# Sheet1.net
KiCad netlist of a schematic drawn in Altium Designer
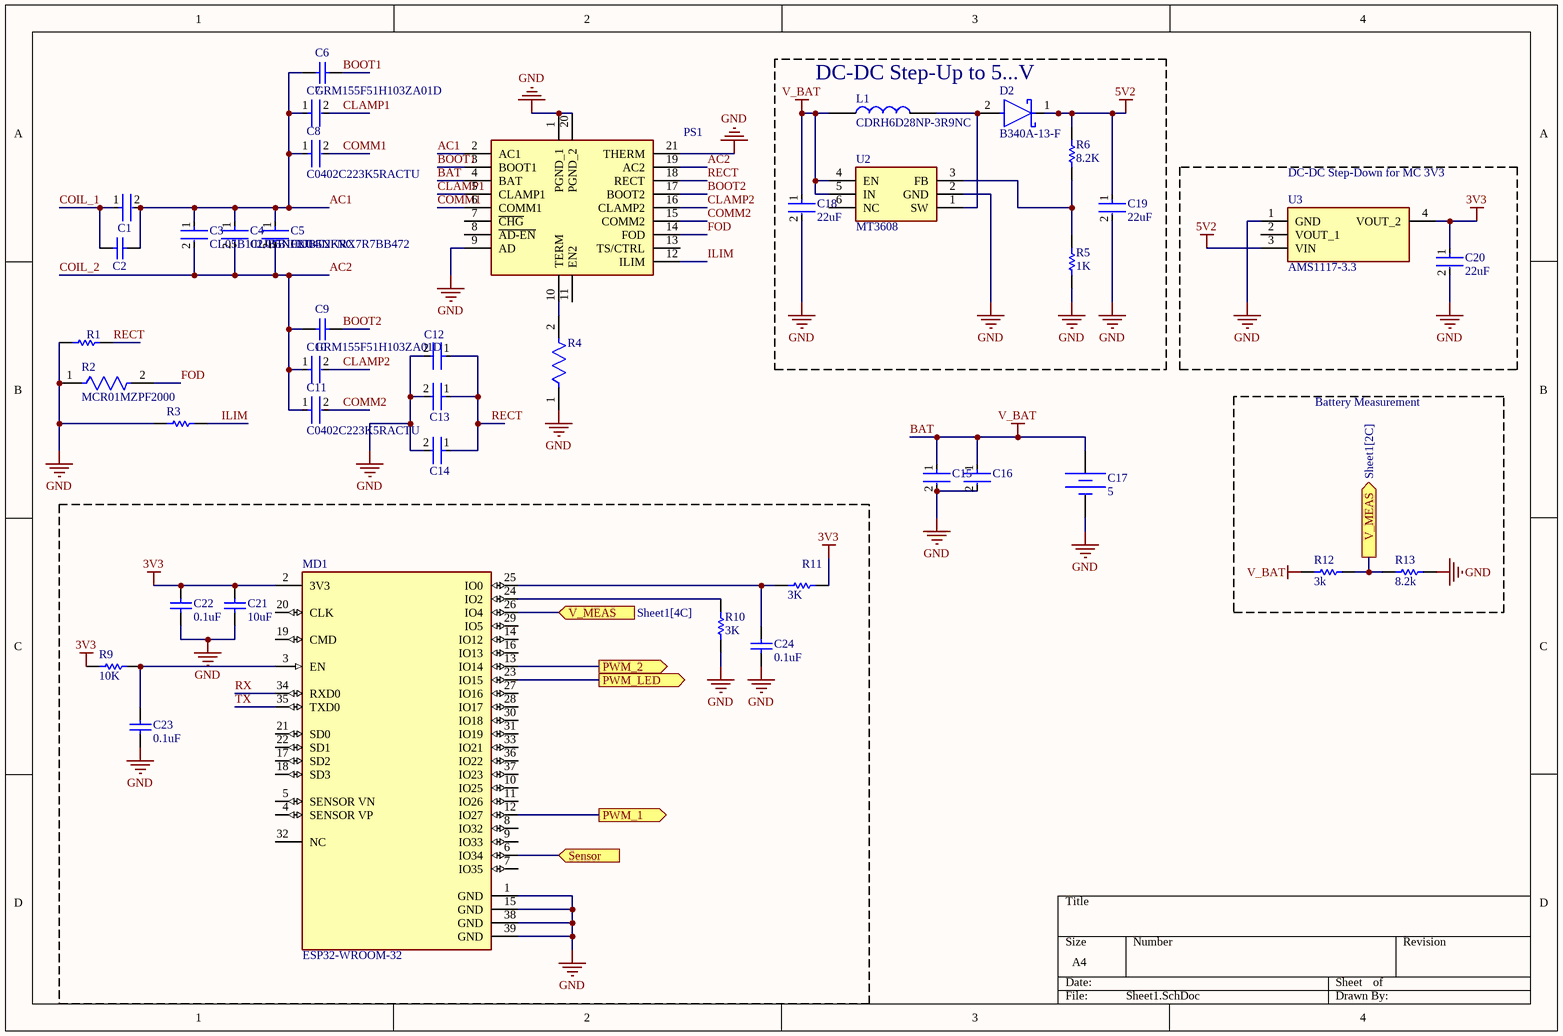
[diagram p0: Sheet1.SchDoc]

(export (version "E")
  (design (tool "Eeschema 10.0.6"))
  (components
    (comp (ref "C1")
      (value "CL05A474KA5NNNC")
      (footprint "FP-CL545-IPC_C")
      (description "Cap Ceramic 470nF 25V X5R ±10% SMD 0402 +85°C Paper T/R")
      (fields (field (name "TOLERANCE") "10%"))
      (libsource (lib "Altium Content Vault") (part "b4654b650e69147ec39a6b967a45e02"))
    )
    (comp (ref "C2")
      (value "04023D104KAT2A")
      (footprint "CAPC1005X56X25NL10T15")
      (fields (field (name "MANUFACTURER") "AVX Interconnect / Elco"))
      (libsource (lib "Altium Content Vault") (part "CAP"))
    )
    (comp (ref "C3")
      (value "CL05B102JB5NFNC")
      (footprint "FP-CL956-IPC_C")
      (description "Cap Ceramic 1nF 50V X7R ±5% SMD 0402 +125°C Paper T/R")
      (fields (field (name "TOLERANCE") "5%"))
      (libsource (lib "Altium Content Vault") (part "b4654b650e69147ec39a6b967a45e02"))
    )
    (comp (ref "C4")
      (value "CL05B102JB5NFNC")
      (footprint "FP-CL956-IPC_C")
      (description "Cap Ceramic 1nF 50V X7R ±5% SMD 0402 +125°C Paper T/R")
      (fields (field (name "TOLERANCE") "5%"))
      (libsource (lib "Altium Content Vault") (part "b4654b650e69147ec39a6b967a45e02"))
    )
    (comp (ref "C5")
      (value "CC0402KRX7R7BB472")
      (footprint "FP-CC0402-MFG")
      (description "CAP CER 4700PF 16V X7R 0402")
      (fields
        (field (name "OCTOPART") "https://octopart.com/cc0402krx7r7bb472-yageo-44648962")
        (field (name "MANUFACTURER") "YAGEO")
      )
      (libsource (lib "Altium Content Vault") (part "11868f565c42a9108669ba33697ecf6"))
    )
    (comp (ref "C6")
      (value "GRM155F51H103ZA01D")
      (footprint "CAPC1005X55X25ML05T10")
      (fields (field (name "MANUFACTURER") "Murata"))
      (libsource (lib "Altium Content Vault") (part "CAP"))
    )
    (comp (ref "C7")
      (value "C1005X5R1E474K050BB")
      (footprint "FP-C1005-050-0_05-IPC_B")
      (description "Multilayer Ceramic Capacitors 470nF ±10% 25V X5R SMD 0402")
      (fields (field (name "VOLTAGE") "25V") (field (name "TOLERANCE") "10%"))
      (libsource (lib "Altium Content Vault") (part "b4654b650e69147ec39a6b967a45e02"))
    )
    (comp (ref "C8")
      (value "C0402C223K5RACTU")
      (footprint "FP-C0402-BB-MFG")
      (description "CAP CER 0.022UF 50V 10% X7R 0402")
      (fields (field (name "TOLERANCE") "0.1") (field (name "MANUFACTURER") "Kemet"))
      (libsource (lib "Altium Content Vault") (part "b4654b650e69147ec39a6b967a45e02"))
    )
    (comp (ref "C9")
      (value "GRM155F51H103ZA01D")
      (footprint "CAPC1005X55X25ML05T10")
      (fields (field (name "MANUFACTURER") "Murata"))
      (libsource (lib "Altium Content Vault") (part "CAP"))
    )
    (comp (ref "C10")
      (value "C1005X5R1E474K050BB")
      (footprint "FP-C1005-050-0_05-IPC_B")
      (description "Multilayer Ceramic Capacitors 470nF ±10% 25V X5R SMD 0402")
      (fields (field (name "VOLTAGE") "25V") (field (name "TOLERANCE") "10%"))
      (libsource (lib "Altium Content Vault") (part "b4654b650e69147ec39a6b967a45e02"))
    )
    (comp (ref "C11")
      (value "C0402C223K5RACTU")
      (footprint "FP-C0402-BB-MFG")
      (description "CAP CER 0.022UF 50V 10% X7R 0402")
      (fields (field (name "TOLERANCE") "0.1") (field (name "MANUFACTURER") "Kemet"))
      (libsource (lib "Altium Content Vault") (part "b4654b650e69147ec39a6b967a45e02"))
    )
    (comp (ref "C12")
      (value "CL10A106MA8NRNC")
      (footprint "FP-CL10-IPC_C")
      (description "Cap Ceramic 10uF 25V X5R ±20% Pad SMD 0603 +85°C T/R")
      (fields (field (name "TOLERANCE") "20%"))
      (libsource (lib "Altium Content Vault") (part "b4654b650e69147ec39a6b967a45e02"))
    )
    (comp (ref "C13")
      (value "CL10A106MA8NRNC")
      (footprint "FP-CL10-IPC_C")
      (description "Cap Ceramic 10uF 25V X5R ±20% Pad SMD 0603 +85°C T/R")
      (fields (field (name "TOLERANCE") "20%"))
      (libsource (lib "Altium Content Vault") (part "b4654b650e69147ec39a6b967a45e02"))
    )
    (comp (ref "C14")
      (value "C0603X5R1E104K030BB")
      (footprint "FP-C0603-030-0_03-IPC_C")
      (description "Multilayer Ceramic Capacitors 100nF ±10% 25V X5R SMD 0201")
      (fields (field (name "TOLERANCE") "10%"))
      (libsource (lib "Altium Content Vault") (part "02cd4be3c70576c341d710602a673aa"))
    )
    (comp (ref "C15")
      (value "EMK105BJ105KV-F")
      (footprint "FP-0402-L_1_0_0_05-W_0_5-IPC_A")
      (description "None")
      (fields (field (name "TOLERANCE") "10%"))
      (libsource (lib "Altium Content Vault") (part "b4654b650e69147ec39a6b967a45e02"))
    )
    (comp (ref "C16")
      (value "GRM033R60J104KE19J")
      (footprint "FP-GRM033-0_03-MFG")
      (description "Chip Multilayer Ceramic Capacitors for General Purpose, 0201, 0.10uF, X5R, 15%, 10%, 6.3V")
      (fields (field (name "TOLERANCE") "10%"))
      (libsource (lib "Altium Content Vault") (part "b4654b650e69147ec39a6b967a45e02"))
    )
    (comp (ref "C17")
      (value "Constant Voltage Source")
      (fields (field (name "DC MAGNITUDE") "5"))
      (libsource (lib "Simulation Generic Components") (part "Battery"))
    )
    (comp (ref "C18")
      (value "22uF")
      (footprint "FP-GRM31C-0_2-e0_3_0_8-IPC_C")
      (description "Chip Multilayer Ceramic Capacitors for General Purpose, 1206, 22uF, X7R, 15%, 10%, 10V")
      (fields (field (name "TOLERANCE") "10%"))
      (libsource (lib "Altium Content Vault") (part "02cd4be3c70576c341d710602a673aa"))
    )
    (comp (ref "C19")
      (value "22uF")
      (footprint "FP-GRM31C-0_2-e0_3_0_8-IPC_C")
      (description "Chip Multilayer Ceramic Capacitors for General Purpose, 1206, 22uF, X7R, 15%, 10%, 10V")
      (fields (field (name "TOLERANCE") "10%"))
      (libsource (lib "Altium Content Vault") (part "02cd4be3c70576c341d710602a673aa"))
    )
    (comp (ref "C20")
      (value "22uF")
      (footprint "FP-GRM31C-0_2-e0_3_0_8-IPC_C")
      (description "Chip Multilayer Ceramic Capacitors for General Purpose, 1206, 22uF, X7R, 15%, 10%, 10V")
      (fields (field (name "TOLERANCE") "10%"))
      (libsource (lib "Altium Content Vault") (part "02cd4be3c70576c341d710602a673aa"))
    )
    (comp (ref "C21")
      (value "10uF")
      (footprint "CAPC1005X55X30LL05T10")
      (fields (field (name "MANUFACTURER") "Kemet") (field (name "PART NUMBER") "C0402C104K4RACTU"))
      (libsource (lib "Altium Content Vault") (part "CAP"))
    )
    (comp (ref "C22")
      (value "0.1uF")
      (footprint "CAPC1005X55X30LL05T10")
      (fields (field (name "MANUFACTURER") "Kemet") (field (name "PART NUMBER") "C0402C104K4RACTU"))
      (libsource (lib "Altium Content Vault") (part "CAP"))
    )
    (comp (ref "C23")
      (value "0.1uF")
      (footprint "CAPC1005X55X30LL05T10")
      (fields (field (name "MANUFACTURER") "Kemet") (field (name "PART NUMBER") "C0402C104K4RACTU"))
      (libsource (lib "Altium Content Vault") (part "CAP"))
    )
    (comp (ref "C24")
      (value "0.1uF")
      (footprint "CAPC1005X55X30LL05T10")
      (fields (field (name "MANUFACTURER") "Kemet") (field (name "PART NUMBER") "C0402C104K4RACTU"))
      (libsource (lib "Altium Content Vault") (part "CAP"))
    )
    (comp (ref "D2")
      (value "B340A-13-F")
      (footprint "FP-SMA-MFG")
      (description "DIODE SCHOTTKY 40V 3A SMA")
      (fields (field (name "VOLTAGE") "40V"))
      (libsource (lib "Altium Content Vault") (part "1d6ec82d83fb6aee721767c19dac4b9"))
    )
    (comp (ref "L1")
      (value "CDRH6D28NP-3R9NC")
      (footprint "INDPM6767X300N")
      (description "Inductor Power Shielded Drum Core 3.9uH 30% 100KHz Ferrite 2.6A 27mOhm DCR T/R")
      (fields (field (name "MOUSER PART NUMBER") "851-CDRH6D28NP-3R9NC"))
      (libsource (lib "CDRH6D28NP-3R9NC") (part "CDRH6D28NP-3R9NC"))
    )
    (comp (ref "MD1")
      (value "ESP32-WROOM-32")
      (footprint "FP-ESP32-WROOM-32-MFG")
      (description "RX TXRX MOD WIFI SURFACE MOUNT")
      (libsource (lib "Altium Content Vault") (part "ee866abf0b6c51247b7f5cdebf2f250"))
    )
    (comp (ref "PS1")
      (value "BQ51050BRHLT")
      (footprint "SamacSys:RHL(R-PVQFN-N20)_1")
      (description "Power Supply")
      (fields (field (name "MOUSER PART NUMBER") "595-BQ51050BRHLT"))
      (libsource (lib "*") (part "BQ51050BRHLT"))
    )
    (comp (ref "R1")
      (value "ERJ-1GNF4122C")
      (footprint "RESC0603X26X15ML03T05")
      (fields (field (name "MANUFACTURER") "Panasonic"))
      (libsource (lib "Altium Content Vault") (part "RES"))
    )
    (comp (ref "R2")
      (value "MCR01MZPF2000")
      (footprint "FP-MCR01-IPC_B")
      (description "Thick Film Chip Resistor, 0402, 200Ω, 1%, 100ppm/°C, 0.063W, 50V")
      (fields (field (name "TOLERANCE") "1%"))
      (libsource (lib "Altium Content Vault") (part "1029c3af85768c4190bb7ad29bc67b5"))
    )
    (comp (ref "R3")
      (value "ERJ-1GEJ391C")
      (footprint "RESC0603X26X15NL03T05")
      (fields (field (name "MANUFACTURER") "Panasonic"))
      (libsource (lib "Altium Content Vault") (part "RES"))
    )
    (comp (ref "R4")
      (value "RMCF0201JT2K40")
      (footprint "FP-RMCF0201-IPC_A")
      (description "2.4kΩ ±5% 0.05W 0201 Thick Film Chip Resistor AEC-Q200 compliant")
      (fields (field (name "TOLERANCE") "5%"))
      (libsource (lib "Altium Content Vault") (part "1029c3af85768c4190bb7ad29bc67b5"))
    )
    (comp (ref "R5")
      (value "1K")
      (footprint "RESC1609X50X30NL8T20")
      (description "Chip Resistor, 0 Ohm, Jumper, 100 mW, -55 to 155 degC, 0603 (1608 Metric), RoHS, Tape and Reel")
      (fields (field (name "MANUFACTURER") "Vishay Semiconductor"))
      (libsource (lib "Altium Content Vault") (part "RES-2"))
    )
    (comp (ref "R6")
      (value "8.2K")
      (footprint "RESC1609X50X30NL8T20")
      (description "Chip Resistor, 0 Ohm, Jumper, 100 mW, -55 to 155 degC, 0603 (1608 Metric), RoHS, Tape and Reel")
      (fields (field (name "MANUFACTURER") "Vishay Semiconductor"))
      (libsource (lib "Altium Content Vault") (part "RES-2"))
    )
    (comp (ref "R9")
      (value "10K")
      (footprint "RESC1609X50X30NL8T20")
      (description "Chip Resistor, 0 Ohm, Jumper, 100 mW, -55 to 155 degC, 0603 (1608 Metric), RoHS, Tape and Reel")
      (fields (field (name "MANUFACTURER") "Vishay Semiconductor"))
      (libsource (lib "Altium Content Vault") (part "RES-2"))
    )
    (comp (ref "R10")
      (value "3K")
      (footprint "RESC1609X50X30NL8T20")
      (description "Chip Resistor, 0 Ohm, Jumper, 100 mW, -55 to 155 degC, 0603 (1608 Metric), RoHS, Tape and Reel")
      (fields (field (name "MANUFACTURER") "Vishay Semiconductor"))
      (libsource (lib "Altium Content Vault") (part "RES-2"))
    )
    (comp (ref "R11")
      (value "3K")
      (footprint "RESC1609X50X30NL8T20")
      (description "Chip Resistor, 0 Ohm, Jumper, 100 mW, -55 to 155 degC, 0603 (1608 Metric), RoHS, Tape and Reel")
      (fields (field (name "MANUFACTURER") "Vishay Semiconductor"))
      (libsource (lib "Altium Content Vault") (part "RES-2"))
    )
    (comp (ref "R12")
      (value "3k")
      (footprint "RESC1609X50X30NL8T20")
      (description "Chip Resistor, 0 Ohm, Jumper, 100 mW, -55 to 155 degC, 0603 (1608 Metric), RoHS, Tape and Reel")
      (fields (field (name "MANUFACTURER") "Vishay Semiconductor"))
      (libsource (lib "Altium Content Vault") (part "RES-2"))
    )
    (comp (ref "R13")
      (value "8.2k")
      (footprint "RESC1609X50X30NL8T20")
      (description "Chip Resistor, 0 Ohm, Jumper, 100 mW, -55 to 155 degC, 0603 (1608 Metric), RoHS, Tape and Reel")
      (fields (field (name "MANUFACTURER") "Vishay Semiconductor"))
      (libsource (lib "Altium Content Vault") (part "RES-2"))
    )
    (comp (ref "U2")
      (value "MT3608")
      (footprint "SOT95P280X145-6N")
      (description "High Efficiency 1.2MHz 2A Step Up Converter")
      (libsource (lib "MT3608") (part "MT3608"))
    )
    (comp (ref "U3")
      (value "AMS1117-3.3")
      (footprint "SOT229P700X180-4N")
      (description "1A LOW DROPOUT VOLTAGE REGULATOR, SOT-223")
      (libsource (lib "AMS1117-3.3") (part "AMS1117-3.3"))
    )
  )
  (nets
    (net (code "1") (name "/AC1") (class "Default")
      (node (ref "C1") (pin "2") (pinfunction "2_2") (pintype "passive"))
      (node (ref "C2") (pin "1") (pinfunction "1_1") (pintype "passive"))
      (node (ref "C3") (pin "1") (pinfunction "1_1") (pintype "passive"))
      (node (ref "C4") (pin "1") (pinfunction "1_1") (pintype "passive"))
      (node (ref "C5") (pin "1") (pinfunction "1_1") (pintype "passive"))
      (node (ref "C6") (pin "1") (pinfunction "1_1") (pintype "passive"))
      (node (ref "C7") (pin "1") (pinfunction "1_1") (pintype "passive"))
      (node (ref "C8") (pin "1") (pinfunction "1_1") (pintype "passive"))
      (node (ref "PS1") (pin "2") (pinfunction "AC1_2") (pintype "passive"))
    )
    (net (code "2") (name "/AC2") (class "Default")
      (node (ref "C10") (pin "1") (pinfunction "1_1") (pintype "passive"))
      (node (ref "C11") (pin "1") (pinfunction "1_1") (pintype "passive"))
      (node (ref "C3") (pin "2") (pinfunction "2_2") (pintype "passive"))
      (node (ref "C4") (pin "2") (pinfunction "2_2") (pintype "passive"))
      (node (ref "C5") (pin "2") (pinfunction "2_2") (pintype "passive"))
      (node (ref "C9") (pin "1") (pinfunction "1_1") (pintype "passive"))
      (node (ref "PS1") (pin "19") (pinfunction "AC2_19") (pintype "passive"))
    )
    (net (code "3") (name "/BOOT1") (class "Default")
      (node (ref "C6") (pin "2") (pinfunction "2_2") (pintype "passive"))
      (node (ref "PS1") (pin "3") (pinfunction "BOOT1_3") (pintype "passive"))
    )
    (net (code "4") (name "/BOOT2") (class "Default")
      (node (ref "C9") (pin "2") (pinfunction "2_2") (pintype "passive"))
      (node (ref "PS1") (pin "17") (pinfunction "BOOT2_17") (pintype "passive"))
    )
    (net (code "5") (name "/CLAMP1") (class "Default")
      (node (ref "C7") (pin "2") (pinfunction "2_2") (pintype "passive"))
      (node (ref "PS1") (pin "5") (pinfunction "CLAMP1_5") (pintype "passive"))
    )
    (net (code "6") (name "/CLAMP2") (class "Default")
      (node (ref "C10") (pin "2") (pinfunction "2_2") (pintype "passive"))
      (node (ref "PS1") (pin "16") (pinfunction "CLAMP2_16") (pintype "passive"))
    )
    (net (code "7") (name "/COIL_1") (class "Default")
      (node (ref "C1") (pin "1") (pinfunction "1_1") (pintype "passive"))
      (node (ref "C2") (pin "2") (pinfunction "2_2") (pintype "passive"))
    )
    (net (code "8") (name "/COMM1") (class "Default")
      (node (ref "C8") (pin "2") (pinfunction "2_2") (pintype "passive"))
      (node (ref "PS1") (pin "6") (pinfunction "COMM1_6") (pintype "passive"))
    )
    (net (code "9") (name "/COMM2") (class "Default")
      (node (ref "C11") (pin "2") (pinfunction "2_2") (pintype "passive"))
      (node (ref "PS1") (pin "15") (pinfunction "COMM2_15") (pintype "passive"))
    )
    (net (code "10") (name "/FOD") (class "Default")
      (node (ref "PS1") (pin "14") (pinfunction "FOD_14") (pintype "passive"))
      (node (ref "R2") (pin "2") (pinfunction "2_2") (pintype "passive"))
    )
    (net (code "11") (name "/ILIM") (class "Default")
      (node (ref "PS1") (pin "12") (pinfunction "ILIM_12") (pintype "passive"))
      (node (ref "R3") (pin "2") (pinfunction "2_2") (pintype "passive"))
    )
    (net (code "12") (name "/PWM_1") (class "Default")
      (node (ref "MD1") (pin "12") (pinfunction "IO27_12") (pintype "bidirectional"))
    )
    (net (code "13") (name "/PWM_2") (class "Default")
      (node (ref "MD1") (pin "13") (pinfunction "IO14_13") (pintype "bidirectional"))
    )
    (net (code "14") (name "/PWM_LED") (class "Default")
      (node (ref "MD1") (pin "23") (pinfunction "IO15_23") (pintype "bidirectional"))
    )
    (net (code "15") (name "/RECT") (class "Default")
      (node (ref "C12") (pin "1") (pinfunction "1_1") (pintype "passive"))
      (node (ref "C13") (pin "1") (pinfunction "1_1") (pintype "passive"))
      (node (ref "C14") (pin "1") (pinfunction "1_1") (pintype "passive"))
      (node (ref "PS1") (pin "18") (pinfunction "RECT_18") (pintype "passive"))
      (node (ref "R1") (pin "2") (pinfunction "2_2") (pintype "passive"))
    )
    (net (code "16") (name "/RX") (class "Default")
      (node (ref "MD1") (pin "34") (pinfunction "RXD0_34") (pintype "bidirectional"))
    )
    (net (code "17") (name "/Sensor") (class "Default")
      (node (ref "MD1") (pin "6") (pinfunction "IO34_6") (pintype "bidirectional"))
    )
    (net (code "18") (name "/TX") (class "Default")
      (node (ref "MD1") (pin "35") (pinfunction "TXD0_35") (pintype "bidirectional"))
    )
    (net (code "19") (name "/V_MEAS") (class "Default")
      (node (ref "MD1") (pin "26") (pinfunction "IO4_26") (pintype "bidirectional"))
      (node (ref "R12") (pin "1") (pinfunction "1_1") (pintype "passive"))
      (node (ref "R13") (pin "2") (pinfunction "2_2") (pintype "passive"))
    )
    (net (code "20") (name "3V3") (class "Default")
      (node (ref "C20") (pin "1") (pinfunction "1_1") (pintype "passive"))
      (node (ref "C21") (pin "2") (pinfunction "2_2") (pintype "passive"))
      (node (ref "C22") (pin "2") (pinfunction "2_2") (pintype "passive"))
      (node (ref "MD1") (pin "2") (pinfunction "3V3_2") (pintype "power_in"))
      (node (ref "R11") (pin "1") (pinfunction "1_1") (pintype "passive"))
      (node (ref "R9") (pin "1") (pinfunction "1_1") (pintype "passive"))
      (node (ref "U3") (pin "4") (pinfunction "VOUT_2_4") (pintype "passive"))
    )
    (net (code "21") (name "5V2") (class "Default")
      (node (ref "C19") (pin "1") (pinfunction "1_1") (pintype "passive"))
      (node (ref "D2") (pin "1") (pinfunction "C_1") (pintype "passive"))
      (node (ref "R6") (pin "2") (pinfunction "2_2") (pintype "passive"))
      (node (ref "U3") (pin "3") (pinfunction "VIN_3") (pintype "passive"))
    )
    (net (code "22") (name "GND") (class "Default")
      (node (ref "C12") (pin "2") (pinfunction "2_2") (pintype "passive"))
      (node (ref "C13") (pin "2") (pinfunction "2_2") (pintype "passive"))
      (node (ref "C14") (pin "2") (pinfunction "2_2") (pintype "passive"))
      (node (ref "C15") (pin "2") (pinfunction "2_2") (pintype "passive"))
      (node (ref "C16") (pin "2") (pinfunction "2_2") (pintype "passive"))
      (node (ref "C17") (pin "2") (pinfunction "2_2") (pintype "passive"))
      (node (ref "C18") (pin "2") (pinfunction "2_2") (pintype "passive"))
      (node (ref "C19") (pin "2") (pinfunction "2_2") (pintype "passive"))
      (node (ref "C20") (pin "2") (pinfunction "2_2") (pintype "passive"))
      (node (ref "C21") (pin "1") (pinfunction "1_1") (pintype "passive"))
      (node (ref "C22") (pin "1") (pinfunction "1_1") (pintype "passive"))
      (node (ref "C23") (pin "1") (pinfunction "1_1") (pintype "passive"))
      (node (ref "C24") (pin "1") (pinfunction "1_1") (pintype "passive"))
      (node (ref "MD1") (pin "1") (pinfunction "GND_1") (pintype "power_in"))
      (node (ref "MD1") (pin "15") (pinfunction "GND_15") (pintype "power_in"))
      (node (ref "MD1") (pin "38") (pinfunction "GND_38") (pintype "power_in"))
      (node (ref "MD1") (pin "39") (pinfunction "GND_39") (pintype "power_in"))
      (node (ref "PS1") (pin "1") (pinfunction "PGND_1_1") (pintype "passive"))
      (node (ref "PS1") (pin "20") (pinfunction "PGND_2_20") (pintype "passive"))
      (node (ref "PS1") (pin "21") (pinfunction "THERM_21") (pintype "passive"))
      (node (ref "PS1") (pin "9") (pinfunction "AD_9") (pintype "passive"))
      (node (ref "R1") (pin "1") (pinfunction "1_1") (pintype "passive"))
      (node (ref "R10") (pin "2") (pinfunction "2_2") (pintype "passive"))
      (node (ref "R13") (pin "1") (pinfunction "1_1") (pintype "passive"))
      (node (ref "R2") (pin "1") (pinfunction "1_1") (pintype "passive"))
      (node (ref "R3") (pin "1") (pinfunction "1_1") (pintype "passive"))
      (node (ref "R4") (pin "1") (pinfunction "1_1") (pintype "passive"))
      (node (ref "R5") (pin "1") (pinfunction "1_1") (pintype "passive"))
      (node (ref "U2") (pin "2") (pinfunction "GND_2") (pintype "passive"))
      (node (ref "U3") (pin "1") (pinfunction "GND_1") (pintype "passive"))
    )
    (net (code "23") (name "Net-(D2-A)") (class "Default")
      (node (ref "D2") (pin "2") (pinfunction "A_2") (pintype "passive"))
      (node (ref "L1") (pin "2") (pinfunction "2_2") (pintype "passive"))
      (node (ref "U2") (pin "1") (pinfunction "SW_1") (pintype "passive"))
    )
    (net (code "24") (name "Net-(MD1-EN)") (class "Default")
      (node (ref "C23") (pin "2") (pinfunction "2_2") (pintype "passive"))
      (node (ref "MD1") (pin "3") (pinfunction "EN_3") (pintype "input"))
      (node (ref "R9") (pin "2") (pinfunction "2_2") (pintype "passive"))
    )
    (net (code "25") (name "Net-(MD1-IO0)") (class "Default")
      (node (ref "C24") (pin "2") (pinfunction "2_2") (pintype "passive"))
      (node (ref "MD1") (pin "25") (pinfunction "IO0_25") (pintype "bidirectional"))
      (node (ref "R11") (pin "2") (pinfunction "2_2") (pintype "passive"))
    )
    (net (code "26") (name "Net-(MD1-IO2)") (class "Default")
      (node (ref "MD1") (pin "24") (pinfunction "IO2_24") (pintype "bidirectional"))
      (node (ref "R10") (pin "1") (pinfunction "1_1") (pintype "passive"))
    )
    (net (code "27") (name "Net-(PS1-TERM)") (class "Default")
      (node (ref "PS1") (pin "10") (pinfunction "TERM_10") (pintype "passive"))
      (node (ref "R4") (pin "2") (pinfunction "2_2") (pintype "passive"))
    )
    (net (code "28") (name "Net-(U2-FB)") (class "Default")
      (node (ref "R5") (pin "2") (pinfunction "2_2") (pintype "passive"))
      (node (ref "R6") (pin "1") (pinfunction "1_1") (pintype "passive"))
      (node (ref "U2") (pin "3") (pinfunction "FB_3") (pintype "passive"))
    )
    (net (code "29") (name "V_BAT") (class "Default")
      (node (ref "C15") (pin "1") (pinfunction "1_1") (pintype "passive"))
      (node (ref "C16") (pin "1") (pinfunction "1_1") (pintype "passive"))
      (node (ref "C17") (pin "1") (pinfunction "1_1") (pintype "passive"))
      (node (ref "C18") (pin "1") (pinfunction "1_1") (pintype "passive"))
      (node (ref "L1") (pin "1") (pinfunction "1_1") (pintype "passive"))
      (node (ref "PS1") (pin "4") (pinfunction "BAT_4") (pintype "passive"))
      (node (ref "R12") (pin "2") (pinfunction "2_2") (pintype "passive"))
      (node (ref "U2") (pin "4") (pinfunction "EN_4") (pintype "passive"))
      (node (ref "U2") (pin "5") (pinfunction "IN_5") (pintype "passive"))
    )
    (net (code "30") (name "unconnected-(MD1-CLK-Pad20)") (class "Default")
      (node (ref "MD1") (pin "20") (pinfunction "CLK_20") (pintype "bidirectional"))
    )
    (net (code "31") (name "unconnected-(MD1-CMD-Pad19)") (class "Default")
      (node (ref "MD1") (pin "19") (pinfunction "CMD_19") (pintype "bidirectional"))
    )
    (net (code "32") (name "unconnected-(MD1-IO5-Pad29)") (class "Default")
      (node (ref "MD1") (pin "29") (pinfunction "IO5_29") (pintype "bidirectional"))
    )
    (net (code "33") (name "unconnected-(MD1-IO12-Pad14)") (class "Default")
      (node (ref "MD1") (pin "14") (pinfunction "IO12_14") (pintype "bidirectional"))
    )
    (net (code "34") (name "unconnected-(MD1-IO13-Pad16)") (class "Default")
      (node (ref "MD1") (pin "16") (pinfunction "IO13_16") (pintype "bidirectional"))
    )
    (net (code "35") (name "unconnected-(MD1-IO16-Pad27)") (class "Default")
      (node (ref "MD1") (pin "27") (pinfunction "IO16_27") (pintype "bidirectional"))
    )
    (net (code "36") (name "unconnected-(MD1-IO17-Pad28)") (class "Default")
      (node (ref "MD1") (pin "28") (pinfunction "IO17_28") (pintype "bidirectional"))
    )
    (net (code "37") (name "unconnected-(MD1-IO18-Pad30)") (class "Default")
      (node (ref "MD1") (pin "30") (pinfunction "IO18_30") (pintype "bidirectional"))
    )
    (net (code "38") (name "unconnected-(MD1-IO19-Pad31)") (class "Default")
      (node (ref "MD1") (pin "31") (pinfunction "IO19_31") (pintype "bidirectional"))
    )
    (net (code "39") (name "unconnected-(MD1-IO21-Pad33)") (class "Default")
      (node (ref "MD1") (pin "33") (pinfunction "IO21_33") (pintype "bidirectional"))
    )
    (net (code "40") (name "unconnected-(MD1-IO22-Pad36)") (class "Default")
      (node (ref "MD1") (pin "36") (pinfunction "IO22_36") (pintype "bidirectional"))
    )
    (net (code "41") (name "unconnected-(MD1-IO23-Pad37)") (class "Default")
      (node (ref "MD1") (pin "37") (pinfunction "IO23_37") (pintype "bidirectional"))
    )
    (net (code "42") (name "unconnected-(MD1-IO25-Pad10)") (class "Default")
      (node (ref "MD1") (pin "10") (pinfunction "IO25_10") (pintype "bidirectional"))
    )
    (net (code "43") (name "unconnected-(MD1-IO26-Pad11)") (class "Default")
      (node (ref "MD1") (pin "11") (pinfunction "IO26_11") (pintype "bidirectional"))
    )
    (net (code "44") (name "unconnected-(MD1-IO32-Pad8)") (class "Default")
      (node (ref "MD1") (pin "8") (pinfunction "IO32_8") (pintype "bidirectional"))
    )
    (net (code "45") (name "unconnected-(MD1-IO33-Pad9)") (class "Default")
      (node (ref "MD1") (pin "9") (pinfunction "IO33_9") (pintype "bidirectional"))
    )
    (net (code "46") (name "unconnected-(MD1-IO35-Pad7)") (class "Default")
      (node (ref "MD1") (pin "7") (pinfunction "IO35_7") (pintype "bidirectional"))
    )
    (net (code "47") (name "unconnected-(MD1-NC-Pad32)") (class "Default")
      (node (ref "MD1") (pin "32") (pinfunction "NC_32") (pintype "passive"))
    )
    (net (code "48") (name "unconnected-(MD1-SD0-Pad21)") (class "Default")
      (node (ref "MD1") (pin "21") (pinfunction "SD0_21") (pintype "bidirectional"))
    )
    (net (code "49") (name "unconnected-(MD1-SD1-Pad22)") (class "Default")
      (node (ref "MD1") (pin "22") (pinfunction "SD1_22") (pintype "bidirectional"))
    )
    (net (code "50") (name "unconnected-(MD1-SD2-Pad17)") (class "Default")
      (node (ref "MD1") (pin "17") (pinfunction "SD2_17") (pintype "bidirectional"))
    )
    (net (code "51") (name "unconnected-(MD1-SD3-Pad18)") (class "Default")
      (node (ref "MD1") (pin "18") (pinfunction "SD3_18") (pintype "bidirectional"))
    )
    (net (code "52") (name "unconnected-(MD1-SENSOR_VN-Pad5)") (class "Default")
      (node (ref "MD1") (pin "5") (pinfunction "SENSOR_VN_5") (pintype "bidirectional"))
    )
    (net (code "53") (name "unconnected-(MD1-SENSOR_VP-Pad4)") (class "Default")
      (node (ref "MD1") (pin "4") (pinfunction "SENSOR_VP_4") (pintype "bidirectional"))
    )
    (net (code "54") (name "unconnected-(PS1-EN2-Pad11)") (class "Default")
      (node (ref "PS1") (pin "11") (pinfunction "EN2_11") (pintype "passive"))
    )
    (net (code "55") (name "unconnected-(PS1-TS{slash}CTRL-Pad13)") (class "Default")
      (node (ref "PS1") (pin "13") (pinfunction "TS/CTRL_13") (pintype "passive"))
    )
    (net (code "56") (name "unconnected-(PS1-~{AD-EN}-Pad8)") (class "Default")
      (node (ref "PS1") (pin "8") (pinfunction "~{AD-EN}_8") (pintype "passive"))
    )
    (net (code "57") (name "unconnected-(PS1-~{CHG}-Pad7)") (class "Default")
      (node (ref "PS1") (pin "7") (pinfunction "~{CHG}_7") (pintype "passive"))
    )
    (net (code "58") (name "unconnected-(U2-NC-Pad6)") (class "Default")
      (node (ref "U2") (pin "6") (pinfunction "NC_6") (pintype "passive"))
    )
    (net (code "59") (name "unconnected-(U3-VOUT_1-Pad2)") (class "Default")
      (node (ref "U3") (pin "2") (pinfunction "VOUT_1_2") (pintype "passive"))
    )
  )
)
